# SignalAnalyse.net
KiCad netlist of a schematic drawn in Altium Designer
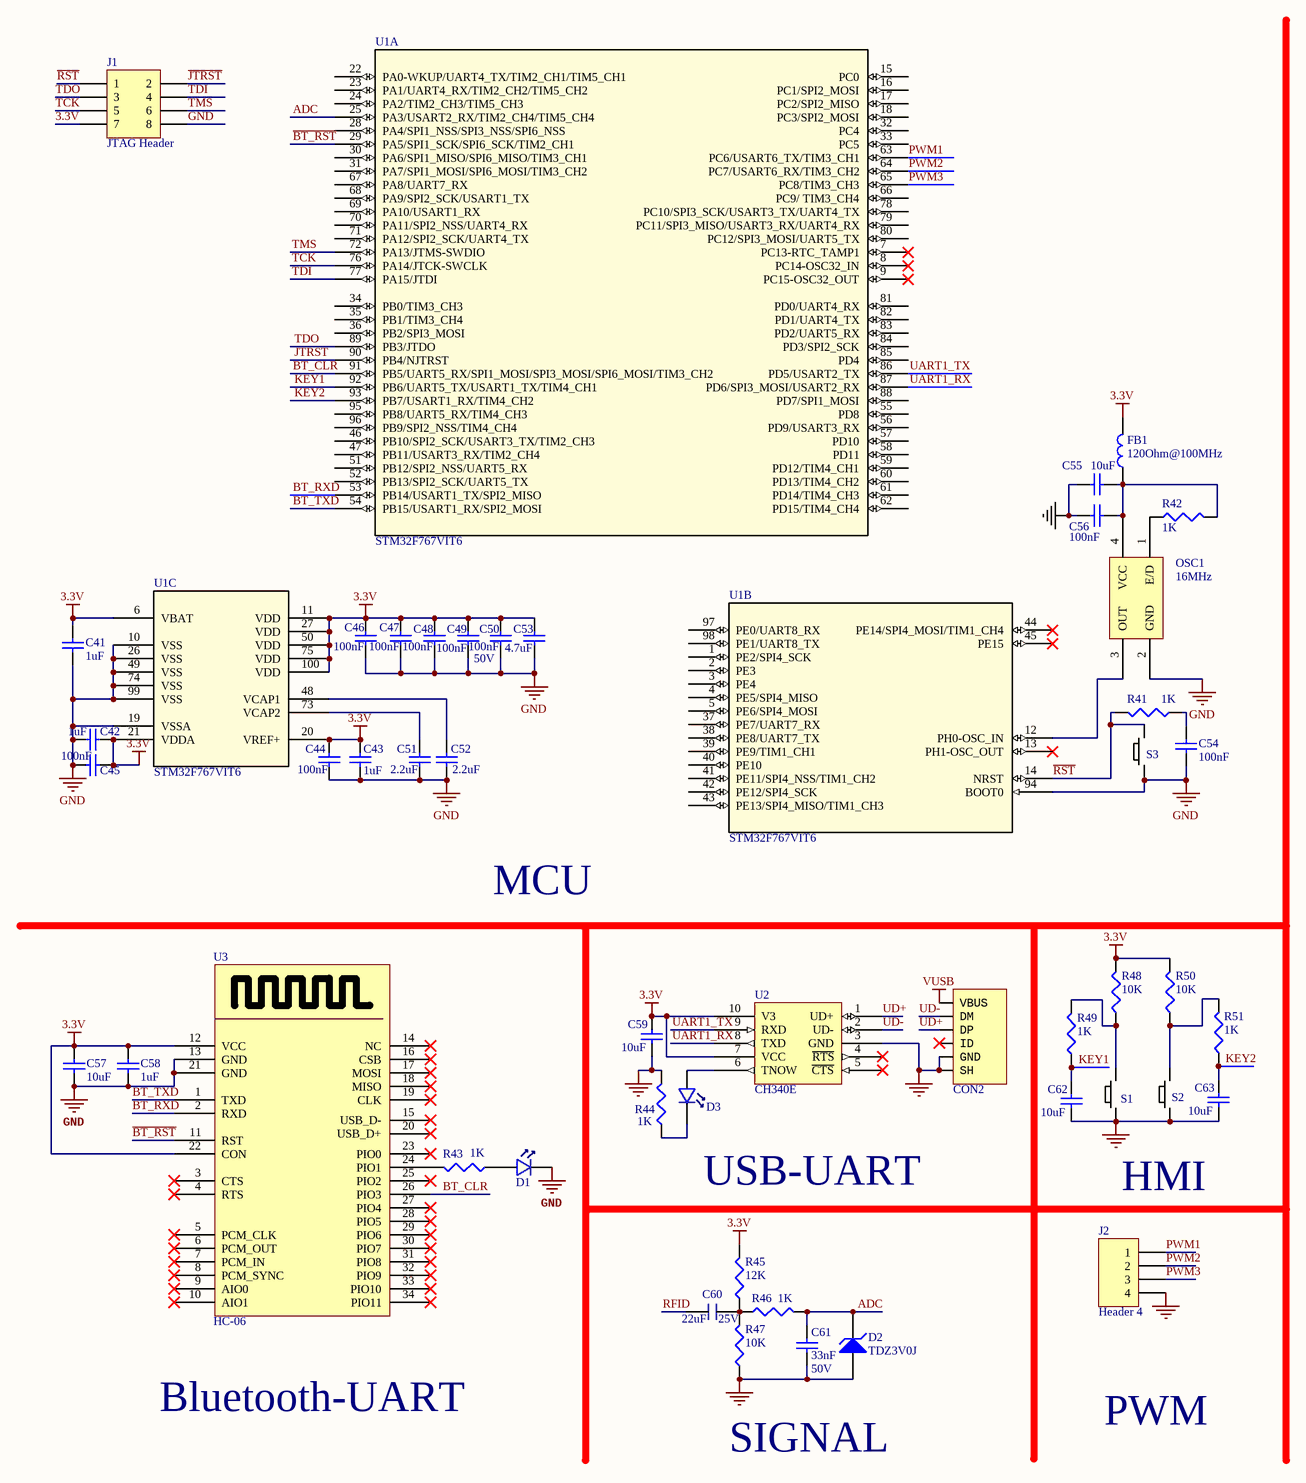
[diagram p0: SignalAnalyse.SchDoc]

(export (version "E")
  (design (tool "Eeschema 10.0.6"))
  (components
    (comp (ref "C41")
      (value "1uF")
      (footprint "1608[0603]")
      (description "Capacitor (Semiconductor SIM Model)")
      (fields
        (field (name "VOLTAGE") "50V")
        (field (name "Comment") "GRM188R61A226ME15D")
        (field (name "PUBLISHER") "Altium Limited")
      )
      (libsource (lib "Miscellaneous Devices") (part "Cap Semi"))
    )
    (comp (ref "C42")
      (value "1uF")
      (footprint "1608[0603]")
      (description "Capacitor (Semiconductor SIM Model)")
      (fields
        (field (name "VOLTAGE") "50V")
        (field (name "Comment") "GRM188R61A226ME15D")
        (field (name "PUBLISHER") "Altium Limited")
      )
      (libsource (lib "Miscellaneous Devices") (part "Cap Semi"))
    )
    (comp (ref "C43")
      (value "1uF")
      (footprint "1608[0603]")
      (description "Capacitor (Semiconductor SIM Model)")
      (fields
        (field (name "VOLTAGE") "50V")
        (field (name "Comment") "GRM188R61A226ME15D")
        (field (name "PUBLISHER") "Altium Limited")
      )
      (libsource (lib "Miscellaneous Devices") (part "Cap Semi"))
    )
    (comp (ref "C44")
      (value "100nF")
      (footprint "1608[0603]")
      (description "Capacitor (Semiconductor SIM Model)")
      (fields
        (field (name "VOLTAGE") "50V")
        (field (name "Comment") "GRM188R61A226ME15D")
        (field (name "PUBLISHER") "Altium Limited")
      )
      (libsource (lib "Miscellaneous Devices") (part "Cap Semi"))
    )
    (comp (ref "C45")
      (value "100nF")
      (footprint "1608[0603]")
      (description "Capacitor (Semiconductor SIM Model)")
      (fields
        (field (name "VOLTAGE") "50V")
        (field (name "Comment") "GRM188R61A226ME15D")
        (field (name "PUBLISHER") "Altium Limited")
      )
      (libsource (lib "Miscellaneous Devices") (part "Cap Semi"))
    )
    (comp (ref "C46")
      (value "100nF")
      (footprint "1608[0603]")
      (description "Capacitor (Semiconductor SIM Model)")
      (fields
        (field (name "VOLTAGE") "50V")
        (field (name "Comment") "GRM188R61A226ME15D")
        (field (name "PUBLISHER") "Altium Limited")
      )
      (libsource (lib "Miscellaneous Devices") (part "Cap Semi"))
    )
    (comp (ref "C47")
      (value "100nF")
      (footprint "1608[0603]")
      (description "Capacitor (Semiconductor SIM Model)")
      (fields
        (field (name "VOLTAGE") "50V")
        (field (name "Comment") "GRM188R61A226ME15D")
        (field (name "PUBLISHER") "Altium Limited")
      )
      (libsource (lib "Miscellaneous Devices") (part "Cap Semi"))
    )
    (comp (ref "C48")
      (value "100nF")
      (footprint "1608[0603]")
      (description "Capacitor (Semiconductor SIM Model)")
      (fields
        (field (name "VOLTAGE") "50V")
        (field (name "Comment") "GRM188R61A226ME15D")
        (field (name "PUBLISHER") "Altium Limited")
      )
      (libsource (lib "Miscellaneous Devices") (part "Cap Semi"))
    )
    (comp (ref "C49")
      (value "100nF")
      (footprint "1608[0603]")
      (description "Capacitor (Semiconductor SIM Model)")
      (fields
        (field (name "VOLTAGE") "50V")
        (field (name "Comment") "GRM188R61A226ME15D")
        (field (name "PUBLISHER") "Altium Limited")
      )
      (libsource (lib "Miscellaneous Devices") (part "Cap Semi"))
    )
    (comp (ref "C50")
      (value "100nF")
      (footprint "1608[0603]")
      (description "Capacitor (Semiconductor SIM Model)")
      (fields
        (field (name "VOLTAGE") "50V")
        (field (name "Comment") "GRM188R61A226ME15D")
        (field (name "PUBLISHER") "Altium Limited")
      )
      (libsource (lib "Miscellaneous Devices") (part "Cap Semi"))
    )
    (comp (ref "C51")
      (value "2.2uF")
      (footprint "1608[0603]")
      (description "Capacitor (Semiconductor SIM Model)")
      (fields
        (field (name "VOLTAGE") "16V")
        (field (name "Comment") "GRM188R61A226ME15D")
        (field (name "PUBLISHER") "Altium Limited")
      )
      (libsource (lib "Miscellaneous Devices") (part "Cap Semi"))
    )
    (comp (ref "C52")
      (value "2.2uF")
      (footprint "1608[0603]")
      (description "Capacitor (Semiconductor SIM Model)")
      (fields
        (field (name "VOLTAGE") "16V")
        (field (name "Comment") "GRM188R61A226ME15D")
        (field (name "PUBLISHER") "Altium Limited")
      )
      (libsource (lib "Miscellaneous Devices") (part "Cap Semi"))
    )
    (comp (ref "C53")
      (value "4.7uF")
      (footprint "1608[0603]")
      (description "Capacitor (Semiconductor SIM Model)")
      (fields
        (field (name "VOLTAGE") "10V")
        (field (name "Comment") "GRM188R61A226ME15D")
        (field (name "PUBLISHER") "Altium Limited")
      )
      (libsource (lib "Miscellaneous Devices") (part "Cap Semi"))
    )
    (comp (ref "C54")
      (value "100nF")
      (footprint "1608[0603]")
      (description "Capacitor (Semiconductor SIM Model)")
      (fields
        (field (name "VOLTAGE") "50V")
        (field (name "Comment") "GRM188R61A226ME15D")
        (field (name "PUBLISHER") "Altium Limited")
      )
      (libsource (lib "Miscellaneous Devices") (part "Cap Semi"))
    )
    (comp (ref "C55")
      (value "10uF")
      (footprint "1608[0603]")
      (description "Capacitor (Semiconductor SIM Model)")
      (fields
        (field (name "VOLTAGE") "10V")
        (field (name "Comment") "GRM188R61A226ME15D")
        (field (name "PUBLISHER") "Altium Limited")
      )
      (libsource (lib "Miscellaneous Devices") (part "Cap Semi"))
    )
    (comp (ref "C56")
      (value "100nF")
      (footprint "1608[0603]")
      (description "Capacitor (Semiconductor SIM Model)")
      (fields
        (field (name "VOLTAGE") "50V")
        (field (name "Comment") "GRM188R61A226ME15D")
        (field (name "PUBLISHER") "Altium Limited")
      )
      (libsource (lib "Miscellaneous Devices") (part "Cap Semi"))
    )
    (comp (ref "C57")
      (value "10uF")
      (footprint "1608[0603]")
      (description "Capacitor (Semiconductor SIM Model)")
      (fields
        (field (name "VOLTAGE") "10V")
        (field (name "Comment") "GRM188R61A226ME15D")
        (field (name "PUBLISHER") "Altium Limited")
      )
      (libsource (lib "Miscellaneous Devices") (part "Cap Semi"))
    )
    (comp (ref "C58")
      (value "1uF")
      (footprint "1608[0603]")
      (description "Capacitor (Semiconductor SIM Model)")
      (fields
        (field (name "VOLTAGE") "50V")
        (field (name "Comment") "GRM188R61A226ME15D")
        (field (name "PUBLISHER") "Altium Limited")
      )
      (libsource (lib "Miscellaneous Devices") (part "Cap Semi"))
    )
    (comp (ref "C59")
      (value "10uF")
      (footprint "1608[0603]")
      (description "Capacitor (Semiconductor SIM Model)")
      (fields
        (field (name "VOLTAGE") "10V")
        (field (name "Comment") "GRM188R61A226ME15D")
        (field (name "PUBLISHER") "Altium Limited")
      )
      (libsource (lib "Miscellaneous Devices") (part "Cap Semi"))
    )
    (comp (ref "C60")
      (value "22uF")
      (footprint "C0805")
      (fields (field (name "VOLTAGE") "25V") (field (name "Comment") "Cap Ceramic"))
      (libsource (lib "Integrated_Library") (part "C-Ceramic"))
    )
    (comp (ref "C61")
      (value "33nF")
      (footprint "1608[0603]")
      (description "Capacitor (Semiconductor SIM Model)")
      (fields
        (field (name "VOLTAGE") "50V")
        (field (name "Comment") "Cap Semi")
        (field (name "PUBLISHER") "Altium Limited")
      )
      (libsource (lib "Miscellaneous Devices") (part "Cap Semi"))
    )
    (comp (ref "C62")
      (value "10uF")
      (footprint "1608[0603]")
      (description "Capacitor (Semiconductor SIM Model)")
      (fields
        (field (name "VOLTAGE") "10V")
        (field (name "Comment") "GRM188R61A226ME15D")
        (field (name "PUBLISHER") "Altium Limited")
      )
      (libsource (lib "Miscellaneous Devices") (part "Cap Semi"))
    )
    (comp (ref "C63")
      (value "10uF")
      (footprint "1608[0603]")
      (description "Capacitor (Semiconductor SIM Model)")
      (fields
        (field (name "VOLTAGE") "10V")
        (field (name "Comment") "GRM188R61A226ME15D")
        (field (name "PUBLISHER") "Altium Limited")
      )
      (libsource (lib "Miscellaneous Devices") (part "Cap Semi"))
    )
    (comp (ref "CON2")
      (value "MicroUSB")
      (footprint "PCB_USB:USB_Micro-AB")
      (description "USB")
      (libsource (lib "SCH_USB") (part "USB_Micro"))
    )
    (comp (ref "D1")
      (value "LED")
      (footprint "D0805")
      (description "UWB_TX_LED")
      (libsource (lib "Integrated_Library") (part "LED"))
    )
    (comp (ref "D2")
      (value "TDZ3V0J")
      (footprint "SOD-323")
      (description "Zener Diode 3V")
      (fields (field (name "PUBLISHER") "Altium Limited"))
      (libsource (lib "Miscellaneous Devices") (part "D Zener"))
    )
    (comp (ref "D3")
      (value "LED-Green")
      (footprint "D0805")
      (libsource (lib "Integrated_Library") (part "LED"))
    )
    (comp (ref "FB1")
      (value "120Ohm@100MHz")
      (footprint "L0805")
      (description "CBW201209U121T")
      (libsource (lib "Integrated_Library") (part "FB"))
    )
    (comp (ref "J1")
      (value "JTAG Header")
      (footprint "HDR2X4")
      (description "Header, 4-Pin, Dual row")
      (fields (field (name "PUBLISHER") "Altium Limited"))
      (libsource (lib "Miscellaneous Connectors") (part "Header 4X2"))
    )
    (comp (ref "J2")
      (value "Header 4")
      (footprint "HDR1X4")
      (description "Header, 4-Pin")
      (fields (field (name "PUBLISHER") "Altium Limited"))
      (libsource (lib "Miscellaneous Connectors") (part "Header 4"))
    )
    (comp (ref "OSC1")
      (value "16MHz")
      (footprint "OSC_3.2X2.5")
      (description "OSC with disable function")
      (libsource (lib "Integrated_Library") (part "OSC2"))
    )
    (comp (ref "R41")
      (value "1K")
      (footprint "J1-0603")
      (description "Resistor")
      (fields (field (name "Comment") "Res") (field (name "PUBLISHER") "Altium Limited"))
      (libsource (lib "Miscellaneous Devices") (part "Res3"))
    )
    (comp (ref "R42")
      (value "1K")
      (footprint "J1-0603")
      (description "Resistor")
      (fields (field (name "Comment") "Res") (field (name "PUBLISHER") "Altium Limited"))
      (libsource (lib "Miscellaneous Devices") (part "Res3"))
    )
    (comp (ref "R43")
      (value "1K")
      (footprint "J1-0603")
      (description "Resistor")
      (fields (field (name "Comment") "Res") (field (name "PUBLISHER") "Altium Limited"))
      (libsource (lib "Miscellaneous Devices") (part "Res3"))
    )
    (comp (ref "R44")
      (value "1K")
      (footprint "J1-0603")
      (description "Resistor")
      (fields (field (name "Comment") "Res") (field (name "PUBLISHER") "Altium Limited"))
      (libsource (lib "Miscellaneous Devices") (part "Res3"))
    )
    (comp (ref "R45")
      (value "12K")
      (footprint "J1-0603")
      (description "Resistor")
      (fields (field (name "Comment") "Res") (field (name "PUBLISHER") "Altium Limited"))
      (libsource (lib "Miscellaneous Devices") (part "Res3"))
    )
    (comp (ref "R46")
      (value "1K")
      (footprint "J1-0603")
      (description "Resistor")
      (fields (field (name "Comment") "Res") (field (name "PUBLISHER") "Altium Limited"))
      (libsource (lib "Miscellaneous Devices") (part "Res3"))
    )
    (comp (ref "R47")
      (value "10K")
      (footprint "J1-0603")
      (description "Resistor")
      (fields (field (name "Comment") "Res") (field (name "PUBLISHER") "Altium Limited"))
      (libsource (lib "Miscellaneous Devices") (part "Res3"))
    )
    (comp (ref "R48")
      (value "10K")
      (footprint "J1-0603")
      (description "Resistor")
      (fields (field (name "Comment") "Res") (field (name "PUBLISHER") "Altium Limited"))
      (libsource (lib "Miscellaneous Devices") (part "Res3"))
    )
    (comp (ref "R49")
      (value "1K")
      (footprint "J1-0603")
      (description "Resistor")
      (fields (field (name "Comment") "Res") (field (name "PUBLISHER") "Altium Limited"))
      (libsource (lib "Miscellaneous Devices") (part "Res3"))
    )
    (comp (ref "R50")
      (value "10K")
      (footprint "J1-0603")
      (description "Resistor")
      (fields (field (name "Comment") "Res") (field (name "PUBLISHER") "Altium Limited"))
      (libsource (lib "Miscellaneous Devices") (part "Res3"))
    )
    (comp (ref "R51")
      (value "1K")
      (footprint "J1-0603")
      (description "Resistor")
      (fields (field (name "Comment") "Res") (field (name "PUBLISHER") "Altium Limited"))
      (libsource (lib "Miscellaneous Devices") (part "Res3"))
    )
    (comp (ref "S1")
      (value "Button")
      (footprint "K2-1107ST-A4SW-06")
      (libsource (lib "Integrated_Library") (part "Button"))
    )
    (comp (ref "S2")
      (value "Button")
      (footprint "K2-1107ST-A4SW-06")
      (libsource (lib "Integrated_Library") (part "Button"))
    )
    (comp (ref "S3")
      (value "Button")
      (footprint "K2-1107ST-A4SW-06")
      (libsource (lib "Integrated_Library") (part "Button"))
    )
    (comp (ref "U1")
      (value "STM32F767VIT6")
      (footprint "STM32F767VIT6")
      (description "Imported")
      (fields
        (field (name "MANUFACTURER_PART_NUMBER") "stm32f76xvxt")
        (field (name "COPYRIGHT") "Copyright (C) 2016 Accelerated Designs. All rights reserved")
      )
      (libsource (lib "") (part "STM32F76XVXT_1"))
    )
    (comp (ref "U2")
      (value "CH340E")
      (footprint "CH340E")
      (description "USB-UART Converter")
      (libsource (lib "Integrated_Library") (part "CH340E"))
    )
    (comp (ref "U3")
      (value "HC-06")
      (footprint "HC-06")
      (description "Decawave's DW1000 Ultra Wideband (UWB) transceiver IC")
      (libsource (lib "Integrated_Library") (part "HC-06"))
    )
  )
  (nets
    (net (code "1") (name "/ADC") (class "Default")
      (node (ref "C61") (pin "2") (pinfunction "2_2") (pintype "passive"))
      (node (ref "D2") (pin "2") (pinfunction "K_2") (pintype "passive"))
      (node (ref "R46") (pin "2") (pinfunction "2_2") (pintype "passive"))
      (node (ref "U1") (pin "25") (pinfunction "PA3/USART2_RX/TIM2_CH4/TIM5_CH4_25") (pintype "bidirectional"))
    )
    (net (code "2") (name "/BT_CLR") (class "Default")
      (node (ref "U1") (pin "91") (pinfunction "PB5/UART5_RX/SPI1_MOSI/SPI3_MOSI/SPI6_MOSI/TIM3_CH2_91") (pintype "bidirectional"))
      (node (ref "U3") (pin "26") (pinfunction "PIO3_26") (pintype "passive"))
    )
    (net (code "3") (name "/BT_RXD") (class "Default")
      (node (ref "U1") (pin "53") (pinfunction "PB14/USART1_TX/SPI2_MISO_53") (pintype "bidirectional"))
      (node (ref "U3") (pin "2") (pinfunction "RXD_2") (pintype "passive"))
    )
    (net (code "4") (name "/BT_TXD") (class "Default")
      (node (ref "U1") (pin "54") (pinfunction "PB15/USART1_RX/SPI2_MOSI_54") (pintype "bidirectional"))
      (node (ref "U3") (pin "1") (pinfunction "TXD_1") (pintype "passive"))
    )
    (net (code "5") (name "/KEY1") (class "Default")
      (node (ref "C62") (pin "1") (pinfunction "1_1") (pintype "passive"))
      (node (ref "R49") (pin "1") (pinfunction "1_1") (pintype "passive"))
      (node (ref "U1") (pin "92") (pinfunction "PB6/UART5_TX/USART1_TX/TIM4_CH1_92") (pintype "bidirectional"))
    )
    (net (code "6") (name "/KEY2") (class "Default")
      (node (ref "C63") (pin "1") (pinfunction "1_1") (pintype "passive"))
      (node (ref "R51") (pin "1") (pinfunction "1_1") (pintype "passive"))
      (node (ref "U1") (pin "93") (pinfunction "PB7/USART1_RX/TIM4_CH2_93") (pintype "bidirectional"))
    )
    (net (code "7") (name "/PWM1") (class "Default")
      (node (ref "J2") (pin "1") (pinfunction "1_1") (pintype "passive"))
      (node (ref "U1") (pin "63") (pinfunction "PC6/USART6_TX/TIM3_CH1_63") (pintype "bidirectional"))
    )
    (net (code "8") (name "/PWM2") (class "Default")
      (node (ref "J2") (pin "2") (pinfunction "2_2") (pintype "passive"))
      (node (ref "U1") (pin "64") (pinfunction "PC7/USART6_RX/TIM3_CH2_64") (pintype "bidirectional"))
    )
    (net (code "9") (name "/PWM3") (class "Default")
      (node (ref "J2") (pin "3") (pinfunction "3_3") (pintype "passive"))
      (node (ref "U1") (pin "65") (pinfunction "PC8/TIM3_CH3_65") (pintype "bidirectional"))
    )
    (net (code "10") (name "/RFID") (class "Default")
      (node (ref "C60") (pin "1") (pinfunction "1_1") (pintype "passive"))
    )
    (net (code "11") (name "/TCK") (class "Default")
      (node (ref "J1") (pin "5") (pinfunction "5_5") (pintype "passive"))
      (node (ref "U1") (pin "76") (pinfunction "PA14/JTCK-SWCLK_76") (pintype "bidirectional"))
    )
    (net (code "12") (name "/TDI") (class "Default")
      (node (ref "J1") (pin "4") (pinfunction "4_4") (pintype "passive"))
      (node (ref "U1") (pin "77") (pinfunction "PA15/JTDI_77") (pintype "bidirectional"))
    )
    (net (code "13") (name "/TDO") (class "Default")
      (node (ref "J1") (pin "3") (pinfunction "3_3") (pintype "passive"))
      (node (ref "U1") (pin "89") (pinfunction "PB3/JTDO_89") (pintype "bidirectional"))
    )
    (net (code "14") (name "/TMS") (class "Default")
      (node (ref "J1") (pin "6") (pinfunction "6_6") (pintype "passive"))
      (node (ref "U1") (pin "72") (pinfunction "PA13/JTMS-SWDIO_72") (pintype "bidirectional"))
    )
    (net (code "15") (name "/UART1_RX") (class "Default")
      (node (ref "U1") (pin "87") (pinfunction "PD6/SPI3_MOSI/USART2_RX_87") (pintype "bidirectional"))
      (node (ref "U2") (pin "8") (pinfunction "TXD_8") (pintype "output"))
    )
    (net (code "16") (name "/UART1_TX") (class "Default")
      (node (ref "U1") (pin "86") (pinfunction "PD5/USART2_TX_86") (pintype "bidirectional"))
      (node (ref "U2") (pin "9") (pinfunction "RXD_9") (pintype "input"))
    )
    (net (code "17") (name "/UD+") (class "Default")
      (node (ref "CON2") (pin "3") (pinfunction "DP_3") (pintype "passive"))
      (node (ref "U2") (pin "1") (pinfunction "UD+_1") (pintype "bidirectional"))
    )
    (net (code "18") (name "/UD-") (class "Default")
      (node (ref "CON2") (pin "2") (pinfunction "DM_2") (pintype "passive"))
      (node (ref "U2") (pin "2") (pinfunction "UD-_2") (pintype "bidirectional"))
    )
    (net (code "19") (name "/~{BT_RST}") (class "Default")
      (node (ref "U1") (pin "29") (pinfunction "PA5/SPI1_SCK/SPI6_SCK/TIM2_CH1_29") (pintype "bidirectional"))
      (node (ref "U3") (pin "11") (pinfunction "RST_11") (pintype "passive"))
    )
    (net (code "20") (name "/~{JTRST}") (class "Default")
      (node (ref "J1") (pin "2") (pinfunction "2_2") (pintype "passive"))
      (node (ref "U1") (pin "90") (pinfunction "PB4/NJTRST_90") (pintype "bidirectional"))
    )
    (net (code "21") (name "/~{RST}") (class "Default")
      (node (ref "J1") (pin "1") (pinfunction "1_1") (pintype "passive"))
      (node (ref "R41") (pin "2") (pinfunction "2_2") (pintype "passive"))
      (node (ref "S3") (pin "1") (pinfunction "1_1") (pintype "passive"))
      (node (ref "U1") (pin "14") (pinfunction "NRST_14") (pintype "bidirectional"))
    )
    (net (code "22") (name "3.3V") (class "Default")
      (node (ref "C41") (pin "1") (pinfunction "1_1") (pintype "passive"))
      (node (ref "C42") (pin "1") (pinfunction "1_1") (pintype "passive"))
      (node (ref "C43") (pin "2") (pinfunction "2_2") (pintype "passive"))
      (node (ref "C44") (pin "2") (pinfunction "2_2") (pintype "passive"))
      (node (ref "C45") (pin "1") (pinfunction "1_1") (pintype "passive"))
      (node (ref "C46") (pin "2") (pinfunction "2_2") (pintype "passive"))
      (node (ref "C47") (pin "2") (pinfunction "2_2") (pintype "passive"))
      (node (ref "C48") (pin "2") (pinfunction "2_2") (pintype "passive"))
      (node (ref "C49") (pin "2") (pinfunction "2_2") (pintype "passive"))
      (node (ref "C50") (pin "2") (pinfunction "2_2") (pintype "passive"))
      (node (ref "C53") (pin "2") (pinfunction "2_2") (pintype "passive"))
      (node (ref "C57") (pin "1") (pinfunction "1_1") (pintype "passive"))
      (node (ref "C58") (pin "1") (pinfunction "1_1") (pintype "passive"))
      (node (ref "C59") (pin "1") (pinfunction "1_1") (pintype "passive"))
      (node (ref "FB1") (pin "1") (pinfunction "1_1") (pintype "passive"))
      (node (ref "J1") (pin "7") (pinfunction "7_7") (pintype "passive"))
      (node (ref "R45") (pin "2") (pinfunction "2_2") (pintype "passive"))
      (node (ref "R48") (pin "2") (pinfunction "2_2") (pintype "passive"))
      (node (ref "R50") (pin "2") (pinfunction "2_2") (pintype "passive"))
      (node (ref "U1") (pin "100") (pinfunction "VDD_100") (pintype "power_in"))
      (node (ref "U1") (pin "11") (pinfunction "VDD_11") (pintype "power_in"))
      (node (ref "U1") (pin "20") (pinfunction "VREF+_20") (pintype "power_in"))
      (node (ref "U1") (pin "21") (pinfunction "VDDA_21") (pintype "power_in"))
      (node (ref "U1") (pin "27") (pinfunction "VDD_27") (pintype "power_in"))
      (node (ref "U1") (pin "50") (pinfunction "VDD_50") (pintype "power_in"))
      (node (ref "U1") (pin "6") (pinfunction "VBAT_6") (pintype "power_in"))
      (node (ref "U1") (pin "75") (pinfunction "VDD_75") (pintype "power_in"))
      (node (ref "U2") (pin "10") (pinfunction "V3_10") (pintype "power_in"))
      (node (ref "U2") (pin "7") (pinfunction "VCC_7") (pintype "power_in"))
      (node (ref "U3") (pin "12") (pinfunction "VCC_12") (pintype "passive"))
      (node (ref "U3") (pin "22") (pinfunction "CON_22") (pintype "passive"))
    )
    (net (code "23") (name "GND") (class "Default")
      (node (ref "C41") (pin "2") (pinfunction "2_2") (pintype "passive"))
      (node (ref "C42") (pin "2") (pinfunction "2_2") (pintype "passive"))
      (node (ref "C43") (pin "1") (pinfunction "1_1") (pintype "passive"))
      (node (ref "C44") (pin "1") (pinfunction "1_1") (pintype "passive"))
      (node (ref "C45") (pin "2") (pinfunction "2_2") (pintype "passive"))
      (node (ref "C46") (pin "1") (pinfunction "1_1") (pintype "passive"))
      (node (ref "C47") (pin "1") (pinfunction "1_1") (pintype "passive"))
      (node (ref "C48") (pin "1") (pinfunction "1_1") (pintype "passive"))
      (node (ref "C49") (pin "1") (pinfunction "1_1") (pintype "passive"))
      (node (ref "C50") (pin "1") (pinfunction "1_1") (pintype "passive"))
      (node (ref "C51") (pin "1") (pinfunction "1_1") (pintype "passive"))
      (node (ref "C52") (pin "1") (pinfunction "1_1") (pintype "passive"))
      (node (ref "C53") (pin "1") (pinfunction "1_1") (pintype "passive"))
      (node (ref "C54") (pin "2") (pinfunction "2_2") (pintype "passive"))
      (node (ref "C55") (pin "2") (pinfunction "2_2") (pintype "passive"))
      (node (ref "C56") (pin "2") (pinfunction "2_2") (pintype "passive"))
      (node (ref "C57") (pin "2") (pinfunction "2_2") (pintype "passive"))
      (node (ref "C58") (pin "2") (pinfunction "2_2") (pintype "passive"))
      (node (ref "C59") (pin "2") (pinfunction "2_2") (pintype "passive"))
      (node (ref "C61") (pin "1") (pinfunction "1_1") (pintype "passive"))
      (node (ref "C62") (pin "2") (pinfunction "2_2") (pintype "passive"))
      (node (ref "C63") (pin "2") (pinfunction "2_2") (pintype "passive"))
      (node (ref "CON2") (pin "0") (pinfunction "SH_0") (pintype "passive"))
      (node (ref "CON2") (pin "5") (pinfunction "GND_5") (pintype "passive"))
      (node (ref "D1") (pin "2") (pinfunction "2_2") (pintype "passive"))
      (node (ref "D2") (pin "1") (pinfunction "A_1") (pintype "passive"))
      (node (ref "J1") (pin "8") (pinfunction "8_8") (pintype "passive"))
      (node (ref "J2") (pin "4") (pinfunction "4_4") (pintype "passive"))
      (node (ref "OSC1") (pin "2") (pinfunction "GND_2") (pintype "passive"))
      (node (ref "R44") (pin "2") (pinfunction "2_2") (pintype "passive"))
      (node (ref "R47") (pin "1") (pinfunction "1_1") (pintype "passive"))
      (node (ref "S1") (pin "2") (pinfunction "2_2") (pintype "passive"))
      (node (ref "S2") (pin "2") (pinfunction "2_2") (pintype "passive"))
      (node (ref "S3") (pin "2") (pinfunction "2_2") (pintype "passive"))
      (node (ref "U1") (pin "10") (pinfunction "VSS_10") (pintype "power_in"))
      (node (ref "U1") (pin "19") (pinfunction "VSSA_19") (pintype "power_in"))
      (node (ref "U1") (pin "26") (pinfunction "VSS_26") (pintype "power_in"))
      (node (ref "U1") (pin "49") (pinfunction "VSS_49") (pintype "power_in"))
      (node (ref "U1") (pin "74") (pinfunction "VSS_74") (pintype "power_in"))
      (node (ref "U1") (pin "94") (pinfunction "BOOT0_94") (pintype "input"))
      (node (ref "U1") (pin "99") (pinfunction "VSS_99") (pintype "power_in"))
      (node (ref "U2") (pin "3") (pinfunction "GND_3") (pintype "power_in"))
      (node (ref "U3") (pin "13") (pinfunction "GND_13") (pintype "passive"))
      (node (ref "U3") (pin "21") (pinfunction "GND_21") (pintype "passive"))
    )
    (net (code "24") (name "Net-(C54-Pad1)") (class "Default")
      (node (ref "C54") (pin "1") (pinfunction "1_1") (pintype "passive"))
      (node (ref "R41") (pin "1") (pinfunction "1_1") (pintype "passive"))
    )
    (net (code "25") (name "Net-(C60-Pad2)") (class "Default")
      (node (ref "C60") (pin "2") (pinfunction "2_2") (pintype "passive"))
      (node (ref "R45") (pin "1") (pinfunction "1_1") (pintype "passive"))
      (node (ref "R46") (pin "1") (pinfunction "1_1") (pintype "passive"))
      (node (ref "R47") (pin "2") (pinfunction "2_2") (pintype "passive"))
    )
    (net (code "26") (name "Net-(D1-Pad1)") (class "Default")
      (node (ref "D1") (pin "1") (pinfunction "1_1") (pintype "passive"))
      (node (ref "R43") (pin "1") (pinfunction "1_1") (pintype "passive"))
    )
    (net (code "27") (name "Net-(D3-Pad2)") (class "Default")
      (node (ref "D3") (pin "2") (pinfunction "2_2") (pintype "passive"))
      (node (ref "R44") (pin "1") (pinfunction "1_1") (pintype "passive"))
    )
    (net (code "28") (name "Net-(OSC1-E{slash}D)") (class "Default")
      (node (ref "OSC1") (pin "1") (pinfunction "E/D_1") (pintype "passive"))
      (node (ref "R42") (pin "1") (pinfunction "1_1") (pintype "passive"))
    )
    (net (code "29") (name "Net-(OSC1-OUT)") (class "Default")
      (node (ref "OSC1") (pin "3") (pinfunction "OUT_3") (pintype "passive"))
      (node (ref "U1") (pin "12") (pinfunction "PH0-OSC_IN_12") (pintype "bidirectional"))
    )
    (net (code "30") (name "Net-(OSC1-VCC)") (class "Default")
      (node (ref "C55") (pin "1") (pinfunction "1_1") (pintype "passive"))
      (node (ref "C56") (pin "1") (pinfunction "1_1") (pintype "passive"))
      (node (ref "FB1") (pin "2") (pinfunction "2_2") (pintype "passive"))
      (node (ref "OSC1") (pin "4") (pinfunction "VCC_4") (pintype "passive"))
      (node (ref "R42") (pin "2") (pinfunction "2_2") (pintype "passive"))
    )
    (net (code "31") (name "Net-(R48-Pad1)") (class "Default")
      (node (ref "R48") (pin "1") (pinfunction "1_1") (pintype "passive"))
      (node (ref "R49") (pin "2") (pinfunction "2_2") (pintype "passive"))
      (node (ref "S1") (pin "1") (pinfunction "1_1") (pintype "passive"))
    )
    (net (code "32") (name "Net-(R50-Pad1)") (class "Default")
      (node (ref "R50") (pin "1") (pinfunction "1_1") (pintype "passive"))
      (node (ref "R51") (pin "2") (pinfunction "2_2") (pintype "passive"))
      (node (ref "S2") (pin "1") (pinfunction "1_1") (pintype "passive"))
    )
    (net (code "33") (name "Net-(U1C-VCAP1)") (class "Default")
      (node (ref "C52") (pin "2") (pinfunction "2_2") (pintype "passive"))
      (node (ref "U1") (pin "48") (pinfunction "VCAP1_48") (pintype "power_in"))
    )
    (net (code "34") (name "Net-(U1C-VCAP2)") (class "Default")
      (node (ref "C51") (pin "2") (pinfunction "2_2") (pintype "passive"))
      (node (ref "U1") (pin "73") (pinfunction "VCAP2_73") (pintype "power_in"))
    )
    (net (code "35") (name "Net-(U2-TNOW)") (class "Default")
      (node (ref "D3") (pin "1") (pinfunction "1_1") (pintype "passive"))
      (node (ref "U2") (pin "6") (pinfunction "TNOW_6") (pintype "output"))
    )
    (net (code "36") (name "Net-(U3-PIO1)") (class "Default")
      (node (ref "R43") (pin "2") (pinfunction "2_2") (pintype "passive"))
      (node (ref "U3") (pin "24") (pinfunction "PIO1_24") (pintype "passive"))
    )
    (net (code "37") (name "VUSB") (class "Default")
      (node (ref "CON2") (pin "1") (pinfunction "VBUS_1") (pintype "passive"))
    )
    (net (code "38") (name "unconnected-(CON2-ID-Pad4)") (class "Default")
      (node (ref "CON2") (pin "4") (pinfunction "ID_4") (pintype "passive+no_connect"))
    )
    (net (code "39") (name "unconnected-(U1A-PA0-WKUP{slash}UART4_TX{slash}TIM2_CH1{slash}TIM5_CH1-Pad22)") (class "Default")
      (node (ref "U1") (pin "22") (pinfunction "PA0-WKUP/UART4_TX/TIM2_CH1/TIM5_CH1_22") (pintype "bidirectional"))
    )
    (net (code "40") (name "unconnected-(U1A-PA1{slash}UART4_RX{slash}TIM2_CH2{slash}TIM5_CH2-Pad23)") (class "Default")
      (node (ref "U1") (pin "23") (pinfunction "PA1/UART4_RX/TIM2_CH2/TIM5_CH2_23") (pintype "bidirectional"))
    )
    (net (code "41") (name "unconnected-(U1A-PA2{slash}TIM2_CH3{slash}TIM5_CH3-Pad24)") (class "Default")
      (node (ref "U1") (pin "24") (pinfunction "PA2/TIM2_CH3/TIM5_CH3_24") (pintype "bidirectional"))
    )
    (net (code "42") (name "unconnected-(U1A-PA4{slash}SPI1_NSS{slash}SPI3_NSS{slash}SPI6_NSS-Pad28)") (class "Default")
      (node (ref "U1") (pin "28") (pinfunction "PA4/SPI1_NSS/SPI3_NSS/SPI6_NSS_28") (pintype "bidirectional"))
    )
    (net (code "43") (name "unconnected-(U1A-PA6{slash}SPI1_MISO{slash}SPI6_MISO{slash}TIM3_CH1-Pad30)") (class "Default")
      (node (ref "U1") (pin "30") (pinfunction "PA6/SPI1_MISO/SPI6_MISO/TIM3_CH1_30") (pintype "bidirectional"))
    )
    (net (code "44") (name "unconnected-(U1A-PA7{slash}SPI1_MOSI{slash}SPI6_MOSI{slash}TIM3_CH2-Pad31)") (class "Default")
      (node (ref "U1") (pin "31") (pinfunction "PA7/SPI1_MOSI/SPI6_MOSI/TIM3_CH2_31") (pintype "bidirectional"))
    )
    (net (code "45") (name "unconnected-(U1A-PA8{slash}UART7_RX-Pad67)") (class "Default")
      (node (ref "U1") (pin "67") (pinfunction "PA8/UART7_RX_67") (pintype "bidirectional"))
    )
    (net (code "46") (name "unconnected-(U1A-PA9{slash}SPI2_SCK{slash}USART1_TX-Pad68)") (class "Default")
      (node (ref "U1") (pin "68") (pinfunction "PA9/SPI2_SCK/USART1_TX_68") (pintype "bidirectional"))
    )
    (net (code "47") (name "unconnected-(U1A-PA10{slash}USART1_RX-Pad69)") (class "Default")
      (node (ref "U1") (pin "69") (pinfunction "PA10/USART1_RX_69") (pintype "bidirectional"))
    )
    (net (code "48") (name "unconnected-(U1A-PA11{slash}SPI2_NSS{slash}UART4_RX-Pad70)") (class "Default")
      (node (ref "U1") (pin "70") (pinfunction "PA11/SPI2_NSS/UART4_RX_70") (pintype "bidirectional"))
    )
    (net (code "49") (name "unconnected-(U1A-PA12{slash}SPI2_SCK{slash}UART4_TX-Pad71)") (class "Default")
      (node (ref "U1") (pin "71") (pinfunction "PA12/SPI2_SCK/UART4_TX_71") (pintype "bidirectional"))
    )
    (net (code "50") (name "unconnected-(U1A-PB0{slash}TIM3_CH3-Pad34)") (class "Default")
      (node (ref "U1") (pin "34") (pinfunction "PB0/TIM3_CH3_34") (pintype "bidirectional"))
    )
    (net (code "51") (name "unconnected-(U1A-PB1{slash}TIM3_CH4-Pad35)") (class "Default")
      (node (ref "U1") (pin "35") (pinfunction "PB1/TIM3_CH4_35") (pintype "bidirectional"))
    )
    (net (code "52") (name "unconnected-(U1A-PB2{slash}SPI3_MOSI-Pad36)") (class "Default")
      (node (ref "U1") (pin "36") (pinfunction "PB2/SPI3_MOSI_36") (pintype "bidirectional"))
    )
    (net (code "53") (name "unconnected-(U1A-PB8{slash}UART5_RX{slash}TIM4_CH3-Pad95)") (class "Default")
      (node (ref "U1") (pin "95") (pinfunction "PB8/UART5_RX/TIM4_CH3_95") (pintype "bidirectional"))
    )
    (net (code "54") (name "unconnected-(U1A-PB9{slash}SPI2_NSS{slash}TIM4_CH4-Pad96)") (class "Default")
      (node (ref "U1") (pin "96") (pinfunction "PB9/SPI2_NSS/TIM4_CH4_96") (pintype "bidirectional"))
    )
    (net (code "55") (name "unconnected-(U1A-PB10{slash}SPI2_SCK{slash}USART3_TX{slash}TIM2_CH3-Pad46)") (class "Default")
      (node (ref "U1") (pin "46") (pinfunction "PB10/SPI2_SCK/USART3_TX/TIM2_CH3_46") (pintype "bidirectional"))
    )
    (net (code "56") (name "unconnected-(U1A-PB11{slash}USART3_RX{slash}TIM2_CH4-Pad47)") (class "Default")
      (node (ref "U1") (pin "47") (pinfunction "PB11/USART3_RX/TIM2_CH4_47") (pintype "bidirectional"))
    )
    (net (code "57") (name "unconnected-(U1A-PB12{slash}SPI2_NSS{slash}UART5_RX-Pad51)") (class "Default")
      (node (ref "U1") (pin "51") (pinfunction "PB12/SPI2_NSS/UART5_RX_51") (pintype "bidirectional"))
    )
    (net (code "58") (name "unconnected-(U1A-PB13{slash}SPI2_SCK{slash}UART5_TX-Pad52)") (class "Default")
      (node (ref "U1") (pin "52") (pinfunction "PB13/SPI2_SCK/UART5_TX_52") (pintype "bidirectional"))
    )
    (net (code "59") (name "unconnected-(U1A-PC0-Pad15)") (class "Default")
      (node (ref "U1") (pin "15") (pinfunction "PC0_15") (pintype "bidirectional"))
    )
    (net (code "60") (name "unconnected-(U1A-PC1{slash}SPI2_MOSI-Pad16)") (class "Default")
      (node (ref "U1") (pin "16") (pinfunction "PC1/SPI2_MOSI_16") (pintype "bidirectional"))
    )
    (net (code "61") (name "unconnected-(U1A-PC2{slash}SPI2_MISO-Pad17)") (class "Default")
      (node (ref "U1") (pin "17") (pinfunction "PC2/SPI2_MISO_17") (pintype "bidirectional"))
    )
    (net (code "62") (name "unconnected-(U1A-PC3{slash}SPI2_MOSI-Pad18)") (class "Default")
      (node (ref "U1") (pin "18") (pinfunction "PC3/SPI2_MOSI_18") (pintype "bidirectional"))
    )
    (net (code "63") (name "unconnected-(U1A-PC4-Pad32)") (class "Default")
      (node (ref "U1") (pin "32") (pinfunction "PC4_32") (pintype "bidirectional"))
    )
    (net (code "64") (name "unconnected-(U1A-PC5-Pad33)") (class "Default")
      (node (ref "U1") (pin "33") (pinfunction "PC5_33") (pintype "bidirectional"))
    )
    (net (code "65") (name "unconnected-(U1A-PC9{slash}_TIM3_CH4-Pad66)") (class "Default")
      (node (ref "U1") (pin "66") (pinfunction "PC9/_TIM3_CH4_66") (pintype "bidirectional"))
    )
    (net (code "66") (name "unconnected-(U1A-PC10{slash}SPI3_SCK{slash}USART3_TX{slash}UART4_TX-Pad78)") (class "Default")
      (node (ref "U1") (pin "78") (pinfunction "PC10/SPI3_SCK/USART3_TX/UART4_TX_78") (pintype "bidirectional"))
    )
    (net (code "67") (name "unconnected-(U1A-PC11{slash}SPI3_MISO{slash}USART3_RX{slash}UART4_RX-Pad79)") (class "Default")
      (node (ref "U1") (pin "79") (pinfunction "PC11/SPI3_MISO/USART3_RX/UART4_RX_79") (pintype "bidirectional"))
    )
    (net (code "68") (name "unconnected-(U1A-PC12{slash}SPI3_MOSI{slash}UART5_TX-Pad80)") (class "Default")
      (node (ref "U1") (pin "80") (pinfunction "PC12/SPI3_MOSI/UART5_TX_80") (pintype "bidirectional"))
    )
    (net (code "69") (name "unconnected-(U1A-PC13-RTC_TAMP1-Pad7)") (class "Default")
      (node (ref "U1") (pin "7") (pinfunction "PC13-RTC_TAMP1_7") (pintype "bidirectional+no_connect"))
    )
    (net (code "70") (name "unconnected-(U1A-PC14-OSC32_IN-Pad8)") (class "Default")
      (node (ref "U1") (pin "8") (pinfunction "PC14-OSC32_IN_8") (pintype "bidirectional+no_connect"))
    )
    (net (code "71") (name "unconnected-(U1A-PC15-OSC32_OUT-Pad9)") (class "Default")
      (node (ref "U1") (pin "9") (pinfunction "PC15-OSC32_OUT_9") (pintype "bidirectional+no_connect"))
    )
    (net (code "72") (name "unconnected-(U1A-PD0{slash}UART4_RX-Pad81)") (class "Default")
      (node (ref "U1") (pin "81") (pinfunction "PD0/UART4_RX_81") (pintype "bidirectional"))
    )
    (net (code "73") (name "unconnected-(U1A-PD1{slash}UART4_TX-Pad82)") (class "Default")
      (node (ref "U1") (pin "82") (pinfunction "PD1/UART4_TX_82") (pintype "bidirectional"))
    )
    (net (code "74") (name "unconnected-(U1A-PD2{slash}UART5_RX-Pad83)") (class "Default")
      (node (ref "U1") (pin "83") (pinfunction "PD2/UART5_RX_83") (pintype "bidirectional"))
    )
    (net (code "75") (name "unconnected-(U1A-PD3{slash}SPI2_SCK-Pad84)") (class "Default")
      (node (ref "U1") (pin "84") (pinfunction "PD3/SPI2_SCK_84") (pintype "bidirectional"))
    )
    (net (code "76") (name "unconnected-(U1A-PD4-Pad85)") (class "Default")
      (node (ref "U1") (pin "85") (pinfunction "PD4_85") (pintype "bidirectional"))
    )
    (net (code "77") (name "unconnected-(U1A-PD7{slash}SPI1_MOSI-Pad88)") (class "Default")
      (node (ref "U1") (pin "88") (pinfunction "PD7/SPI1_MOSI_88") (pintype "bidirectional"))
    )
    (net (code "78") (name "unconnected-(U1A-PD8-Pad55)") (class "Default")
      (node (ref "U1") (pin "55") (pinfunction "PD8_55") (pintype "bidirectional"))
    )
    (net (code "79") (name "unconnected-(U1A-PD9{slash}USART3_RX-Pad56)") (class "Default")
      (node (ref "U1") (pin "56") (pinfunction "PD9/USART3_RX_56") (pintype "bidirectional"))
    )
    (net (code "80") (name "unconnected-(U1A-PD10-Pad57)") (class "Default")
      (node (ref "U1") (pin "57") (pinfunction "PD10_57") (pintype "bidirectional"))
    )
    (net (code "81") (name "unconnected-(U1A-PD11-Pad58)") (class "Default")
      (node (ref "U1") (pin "58") (pinfunction "PD11_58") (pintype "bidirectional"))
    )
    (net (code "82") (name "unconnected-(U1A-PD12{slash}TIM4_CH1-Pad59)") (class "Default")
      (node (ref "U1") (pin "59") (pinfunction "PD12/TIM4_CH1_59") (pintype "bidirectional"))
    )
    (net (code "83") (name "unconnected-(U1A-PD13{slash}TIM4_CH2-Pad60)") (class "Default")
      (node (ref "U1") (pin "60") (pinfunction "PD13/TIM4_CH2_60") (pintype "bidirectional"))
    )
    (net (code "84") (name "unconnected-(U1A-PD14{slash}TIM4_CH3-Pad61)") (class "Default")
      (node (ref "U1") (pin "61") (pinfunction "PD14/TIM4_CH3_61") (pintype "bidirectional"))
    )
    (net (code "85") (name "unconnected-(U1A-PD15{slash}TIM4_CH4-Pad62)") (class "Default")
      (node (ref "U1") (pin "62") (pinfunction "PD15/TIM4_CH4_62") (pintype "bidirectional"))
    )
    (net (code "86") (name "unconnected-(U1B-PE0{slash}UART8_RX-Pad97)") (class "Default")
      (node (ref "U1") (pin "97") (pinfunction "PE0/UART8_RX_97") (pintype "bidirectional"))
    )
    (net (code "87") (name "unconnected-(U1B-PE1{slash}UART8_TX-Pad98)") (class "Default")
      (node (ref "U1") (pin "98") (pinfunction "PE1/UART8_TX_98") (pintype "bidirectional"))
    )
    (net (code "88") (name "unconnected-(U1B-PE2{slash}SPI4_SCK-Pad1)") (class "Default")
      (node (ref "U1") (pin "1") (pinfunction "PE2/SPI4_SCK_1") (pintype "bidirectional"))
    )
    (net (code "89") (name "unconnected-(U1B-PE3-Pad2)") (class "Default")
      (node (ref "U1") (pin "2") (pinfunction "PE3_2") (pintype "bidirectional"))
    )
    (net (code "90") (name "unconnected-(U1B-PE4-Pad3)") (class "Default")
      (node (ref "U1") (pin "3") (pinfunction "PE4_3") (pintype "bidirectional"))
    )
    (net (code "91") (name "unconnected-(U1B-PE5{slash}SPI4_MISO-Pad4)") (class "Default")
      (node (ref "U1") (pin "4") (pinfunction "PE5/SPI4_MISO_4") (pintype "bidirectional"))
    )
    (net (code "92") (name "unconnected-(U1B-PE6{slash}SPI4_MOSI-Pad5)") (class "Default")
      (node (ref "U1") (pin "5") (pinfunction "PE6/SPI4_MOSI_5") (pintype "bidirectional"))
    )
    (net (code "93") (name "unconnected-(U1B-PE7{slash}UART7_RX-Pad37)") (class "Default")
      (node (ref "U1") (pin "37") (pinfunction "PE7/UART7_RX_37") (pintype "bidirectional"))
    )
    (net (code "94") (name "unconnected-(U1B-PE8{slash}UART7_TX-Pad38)") (class "Default")
      (node (ref "U1") (pin "38") (pinfunction "PE8/UART7_TX_38") (pintype "bidirectional"))
    )
    (net (code "95") (name "unconnected-(U1B-PE9{slash}TIM1_CH1-Pad39)") (class "Default")
      (node (ref "U1") (pin "39") (pinfunction "PE9/TIM1_CH1_39") (pintype "bidirectional"))
    )
    (net (code "96") (name "unconnected-(U1B-PE10-Pad40)") (class "Default")
      (node (ref "U1") (pin "40") (pinfunction "PE10_40") (pintype "bidirectional"))
    )
    (net (code "97") (name "unconnected-(U1B-PE11{slash}SPI4_NSS{slash}TIM1_CH2-Pad41)") (class "Default")
      (node (ref "U1") (pin "41") (pinfunction "PE11/SPI4_NSS/TIM1_CH2_41") (pintype "bidirectional"))
    )
    (net (code "98") (name "unconnected-(U1B-PE12{slash}SPI4_SCK-Pad42)") (class "Default")
      (node (ref "U1") (pin "42") (pinfunction "PE12/SPI4_SCK_42") (pintype "bidirectional"))
    )
    (net (code "99") (name "unconnected-(U1B-PE13{slash}SPI4_MISO{slash}TIM1_CH3-Pad43)") (class "Default")
      (node (ref "U1") (pin "43") (pinfunction "PE13/SPI4_MISO/TIM1_CH3_43") (pintype "bidirectional"))
    )
    (net (code "100") (name "unconnected-(U1B-PE14{slash}SPI4_MOSI{slash}TIM1_CH4-Pad44)") (class "Default")
      (node (ref "U1") (pin "44") (pinfunction "PE14/SPI4_MOSI/TIM1_CH4_44") (pintype "bidirectional+no_connect"))
    )
    (net (code "101") (name "unconnected-(U1B-PE15-Pad45)") (class "Default")
      (node (ref "U1") (pin "45") (pinfunction "PE15_45") (pintype "bidirectional+no_connect"))
    )
    (net (code "102") (name "unconnected-(U1B-PH1-OSC_OUT-Pad13)") (class "Default")
      (node (ref "U1") (pin "13") (pinfunction "PH1-OSC_OUT_13") (pintype "bidirectional+no_connect"))
    )
    (net (code "103") (name "unconnected-(U2-~{CTS}-Pad5)") (class "Default")
      (node (ref "U2") (pin "5") (pinfunction "~{CTS}_5") (pintype "input+no_connect"))
    )
    (net (code "104") (name "unconnected-(U2-~{RTS}-Pad4)") (class "Default")
      (node (ref "U2") (pin "4") (pinfunction "~{RTS}_4") (pintype "output+no_connect"))
    )
    (net (code "105") (name "unconnected-(U3-AIO0-Pad9)") (class "Default")
      (node (ref "U3") (pin "9") (pinfunction "AIO0_9") (pintype "passive+no_connect"))
    )
    (net (code "106") (name "unconnected-(U3-AIO1-Pad10)") (class "Default")
      (node (ref "U3") (pin "10") (pinfunction "AIO1_10") (pintype "passive+no_connect"))
    )
    (net (code "107") (name "unconnected-(U3-CLK-Pad19)") (class "Default")
      (node (ref "U3") (pin "19") (pinfunction "CLK_19") (pintype "passive+no_connect"))
    )
    (net (code "108") (name "unconnected-(U3-CSB-Pad16)") (class "Default")
      (node (ref "U3") (pin "16") (pinfunction "CSB_16") (pintype "passive+no_connect"))
    )
    (net (code "109") (name "unconnected-(U3-CTS-Pad3)") (class "Default")
      (node (ref "U3") (pin "3") (pinfunction "CTS_3") (pintype "passive+no_connect"))
    )
    (net (code "110") (name "unconnected-(U3-MISO-Pad18)") (class "Default")
      (node (ref "U3") (pin "18") (pinfunction "MISO_18") (pintype "passive+no_connect"))
    )
    (net (code "111") (name "unconnected-(U3-MOSI-Pad17)") (class "Default")
      (node (ref "U3") (pin "17") (pinfunction "MOSI_17") (pintype "passive+no_connect"))
    )
    (net (code "112") (name "unconnected-(U3-NC-Pad14)") (class "Default")
      (node (ref "U3") (pin "14") (pinfunction "NC_14") (pintype "passive+no_connect"))
    )
    (net (code "113") (name "unconnected-(U3-PCM_CLK-Pad5)") (class "Default")
      (node (ref "U3") (pin "5") (pinfunction "PCM_CLK_5") (pintype "passive+no_connect"))
    )
    (net (code "114") (name "unconnected-(U3-PCM_IN-Pad7)") (class "Default")
      (node (ref "U3") (pin "7") (pinfunction "PCM_IN_7") (pintype "passive+no_connect"))
    )
    (net (code "115") (name "unconnected-(U3-PCM_OUT-Pad6)") (class "Default")
      (node (ref "U3") (pin "6") (pinfunction "PCM_OUT_6") (pintype "passive+no_connect"))
    )
    (net (code "116") (name "unconnected-(U3-PCM_SYNC-Pad8)") (class "Default")
      (node (ref "U3") (pin "8") (pinfunction "PCM_SYNC_8") (pintype "passive+no_connect"))
    )
    (net (code "117") (name "unconnected-(U3-PIO0-Pad23)") (class "Default")
      (node (ref "U3") (pin "23") (pinfunction "PIO0_23") (pintype "passive+no_connect"))
    )
    (net (code "118") (name "unconnected-(U3-PIO2-Pad25)") (class "Default")
      (node (ref "U3") (pin "25") (pinfunction "PIO2_25") (pintype "passive+no_connect"))
    )
    (net (code "119") (name "unconnected-(U3-PIO4-Pad27)") (class "Default")
      (node (ref "U3") (pin "27") (pinfunction "PIO4_27") (pintype "passive+no_connect"))
    )
    (net (code "120") (name "unconnected-(U3-PIO5-Pad28)") (class "Default")
      (node (ref "U3") (pin "28") (pinfunction "PIO5_28") (pintype "passive+no_connect"))
    )
    (net (code "121") (name "unconnected-(U3-PIO6-Pad29)") (class "Default")
      (node (ref "U3") (pin "29") (pinfunction "PIO6_29") (pintype "passive+no_connect"))
    )
    (net (code "122") (name "unconnected-(U3-PIO7-Pad30)") (class "Default")
      (node (ref "U3") (pin "30") (pinfunction "PIO7_30") (pintype "passive+no_connect"))
    )
    (net (code "123") (name "unconnected-(U3-PIO8-Pad31)") (class "Default")
      (node (ref "U3") (pin "31") (pinfunction "PIO8_31") (pintype "passive+no_connect"))
    )
    (net (code "124") (name "unconnected-(U3-PIO9-Pad32)") (class "Default")
      (node (ref "U3") (pin "32") (pinfunction "PIO9_32") (pintype "passive+no_connect"))
    )
    (net (code "125") (name "unconnected-(U3-PIO10-Pad33)") (class "Default")
      (node (ref "U3") (pin "33") (pinfunction "PIO10_33") (pintype "passive+no_connect"))
    )
    (net (code "126") (name "unconnected-(U3-PIO11-Pad34)") (class "Default")
      (node (ref "U3") (pin "34") (pinfunction "PIO11_34") (pintype "passive+no_connect"))
    )
    (net (code "127") (name "unconnected-(U3-RTS-Pad4)") (class "Default")
      (node (ref "U3") (pin "4") (pinfunction "RTS_4") (pintype "passive+no_connect"))
    )
    (net (code "128") (name "unconnected-(U3-USB_D+-Pad20)") (class "Default")
      (node (ref "U3") (pin "20") (pinfunction "USB_D+_20") (pintype "passive+no_connect"))
    )
    (net (code "129") (name "unconnected-(U3-USB_D--Pad15)") (class "Default")
      (node (ref "U3") (pin "15") (pinfunction "USB_D-_15") (pintype "passive+no_connect"))
    )
  )
)
